# Stepper_Motor3.net
KiCad netlist of a schematic drawn in Altium Designer
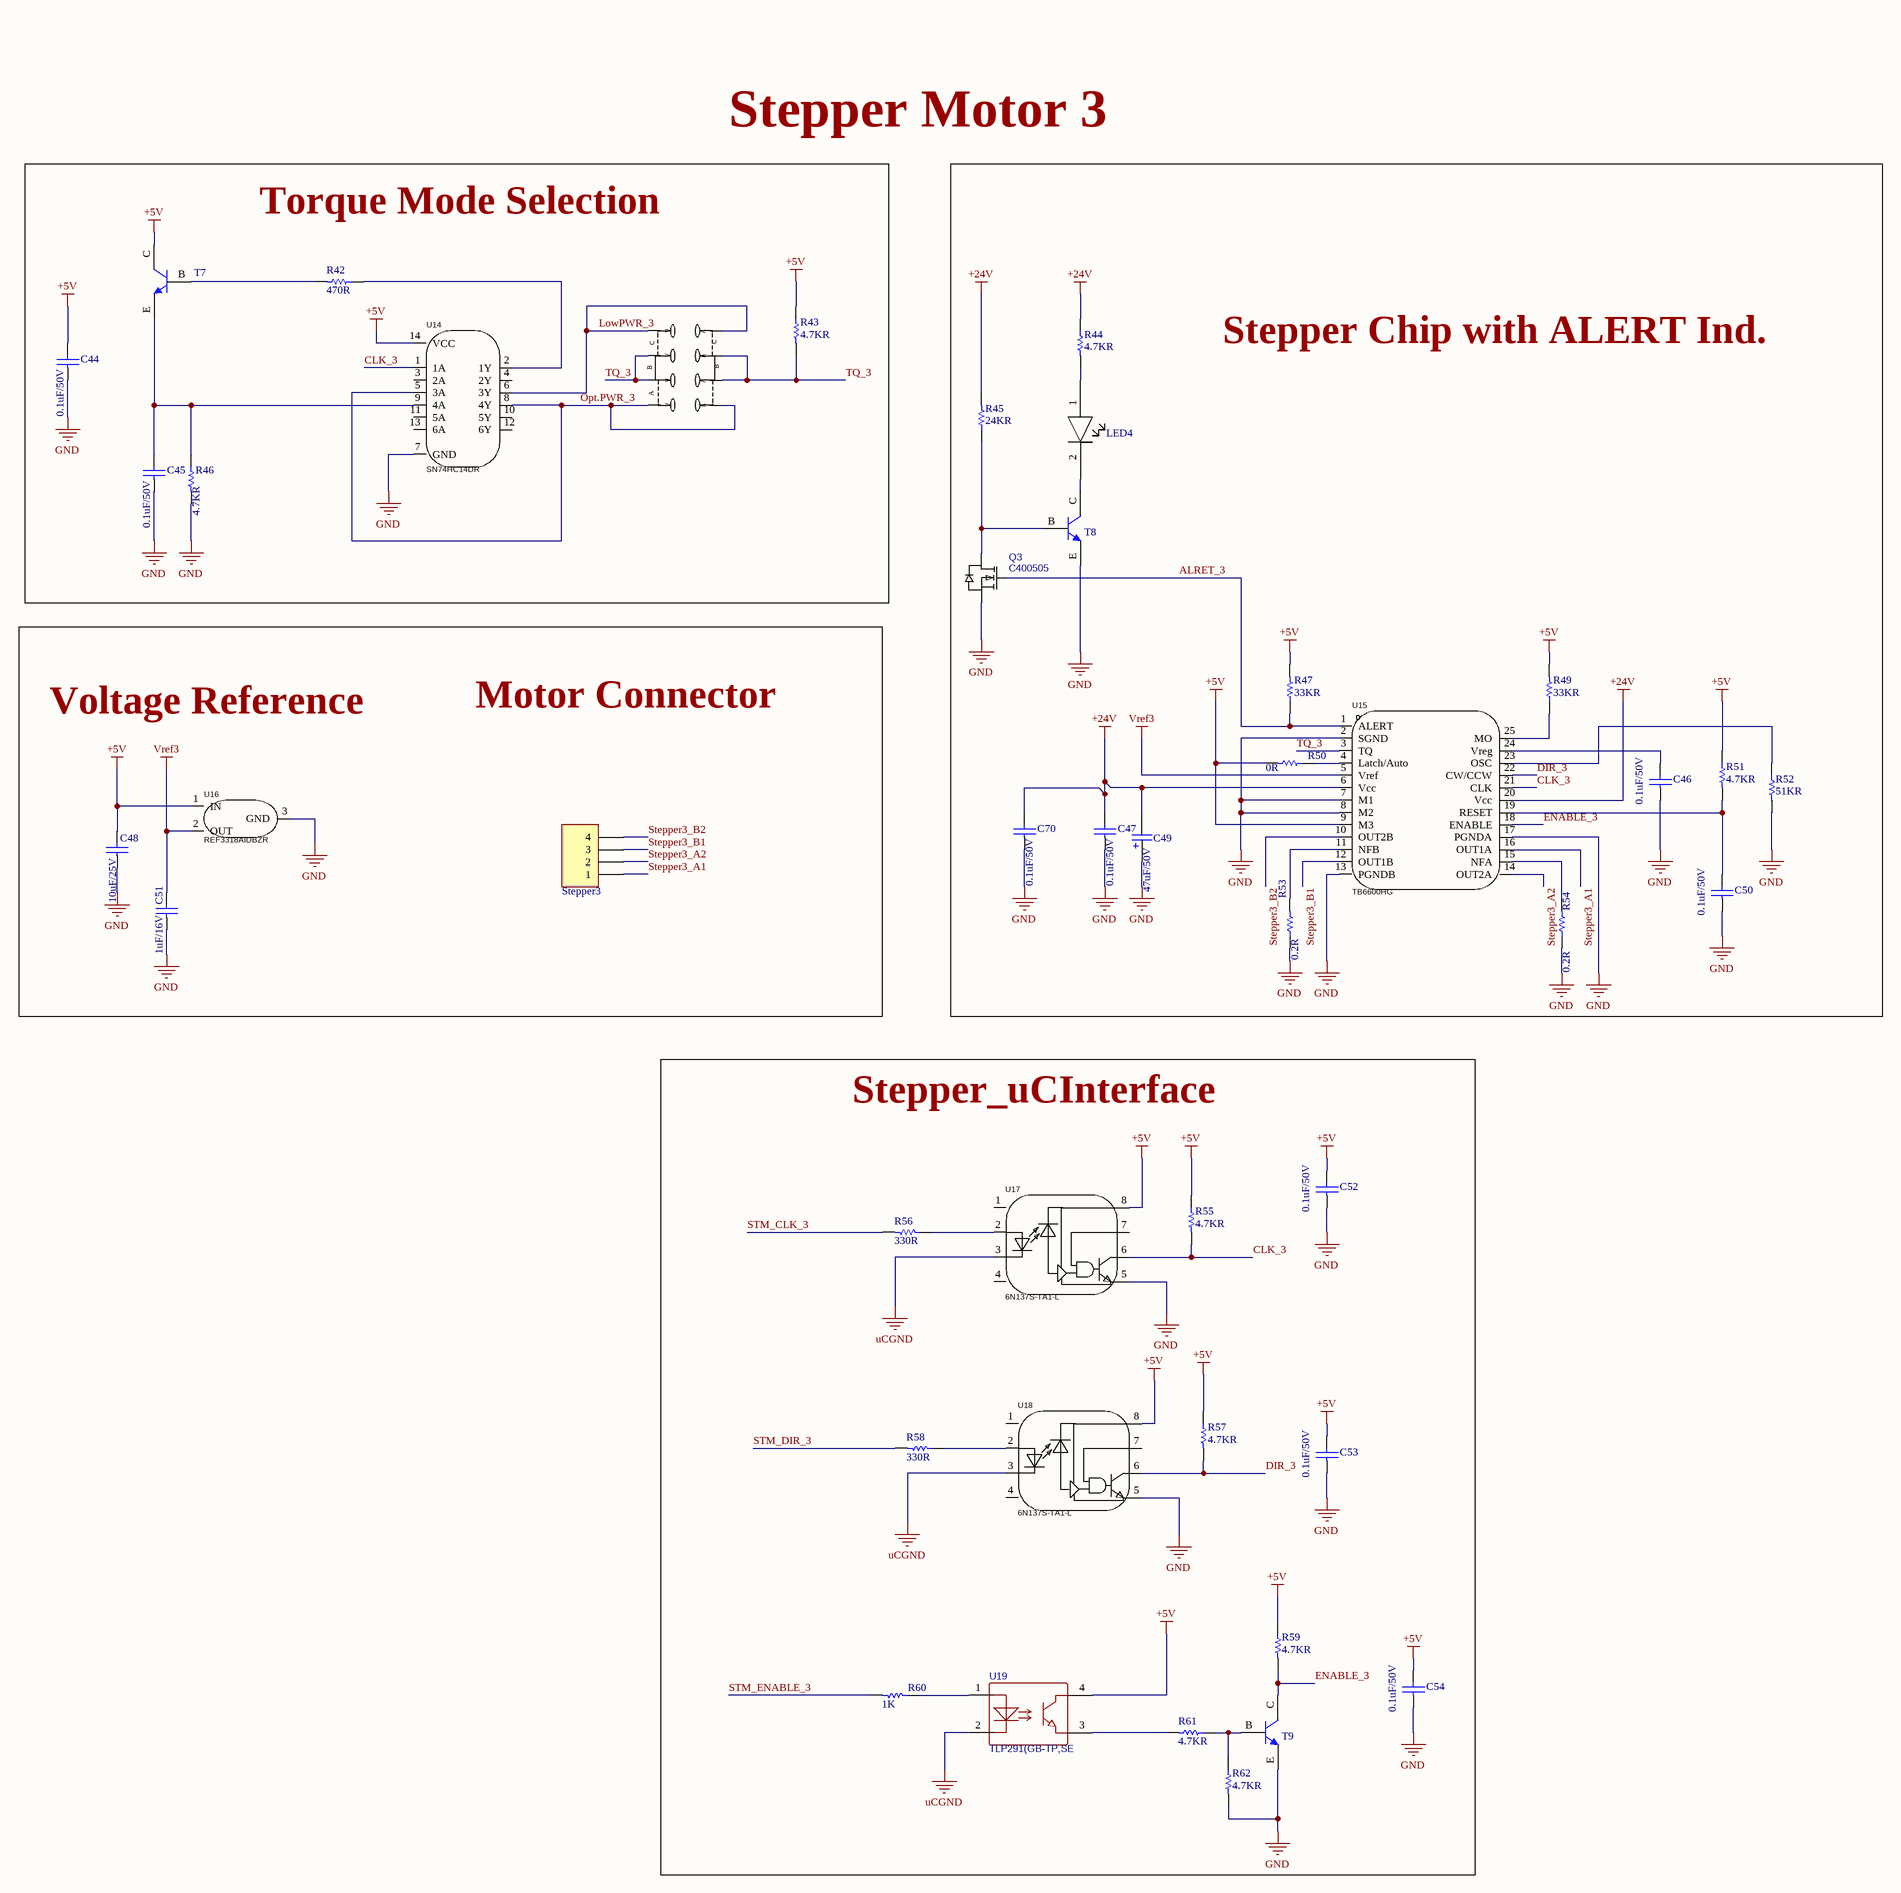
[diagram p0: Stepper Motor3.SchDoc]

(export (version "E")
  (design (tool "Eeschema 10.0.6"))
  (components
    (comp (ref "C44")
      (value "0.1uF/50V")
      (footprint "PCBComponent_1")
      (description "C1591")
      (fields (field (name "CREATED BY") "NourAldin"))
      (libsource (lib "0603 Capacitor") (part "0603 Capacitor"))
    )
    (comp (ref "C45")
      (value "0.1uF/50V")
      (footprint "PCBComponent_1")
      (description "C1591")
      (fields (field (name "CREATED BY") "NourAldin"))
      (libsource (lib "0603 Capacitor") (part "0603 Capacitor"))
    )
    (comp (ref "C46")
      (value "0.1uF/50V")
      (footprint "PCBComponent_1")
      (description "C1591")
      (fields (field (name "CREATED BY") "NourAldin"))
      (libsource (lib "0603 Capacitor") (part "0603 Capacitor"))
    )
    (comp (ref "C47")
      (value "0.1uF/50V")
      (footprint "PCBComponent_1")
      (description "C1591")
      (fields (field (name "CREATED BY") "NourAldin"))
      (libsource (lib "0603 Capacitor") (part "0603 Capacitor"))
    )
    (comp (ref "C48")
      (value "10uF/25V")
      (footprint "PCBComponent_1")
      (description "C96446")
      (fields (field (name "CREATED BY") "NourAldin"))
      (libsource (lib "0603 Capacitor") (part "0603 Capacitor"))
    )
    (comp (ref "C49")
      (value "47uF/50V")
      (footprint "CAPLEAD_D6.3mm")
      (description "C45100")
      (fields
        (field (name "MANUFACTURER") "KEMET")
        (field (name "MANUFACTURER PART NUMBER") "A759EQ475M2AAAE160")
      )
      (libsource (lib "GlobalLib") (part "A759EQ475M2AAAE160"))
    )
    (comp (ref "C50")
      (value "0.1uF/50V")
      (footprint "PCBComponent_1")
      (description "C1591")
      (fields (field (name "CREATED BY") "NourAldin"))
      (libsource (lib "0603 Capacitor") (part "0603 Capacitor"))
    )
    (comp (ref "C51")
      (value "1uF/16V")
      (footprint "PCBComponent_1")
      (description "C1592")
      (fields (field (name "CREATED BY") "NourAldin"))
      (libsource (lib "0603 Capacitor") (part "0603 Capacitor"))
    )
    (comp (ref "C52")
      (value "0.1uF/50V")
      (footprint "PCBComponent_1")
      (description "C1591")
      (fields (field (name "CREATED BY") "NourAldin"))
      (libsource (lib "0603 Capacitor") (part "0603 Capacitor"))
    )
    (comp (ref "C53")
      (value "0.1uF/50V")
      (footprint "PCBComponent_1")
      (description "C1591")
      (fields (field (name "CREATED BY") "NourAldin"))
      (libsource (lib "0603 Capacitor") (part "0603 Capacitor"))
    )
    (comp (ref "C54")
      (value "0.1uF/50V")
      (footprint "PCBComponent_1")
      (description "C1591")
      (fields (field (name "CREATED BY") "NourAldin"))
      (libsource (lib "0603 Capacitor") (part "0603 Capacitor"))
    )
    (comp (ref "C70")
      (value "0.1uF/50V")
      (footprint "PCBComponent_1")
      (description "C1591")
      (fields (field (name "CREATED BY") "NourAldin"))
      (libsource (lib "0603 Capacitor") (part "0603 Capacitor"))
    )
    (comp (ref "LED4")
      (value "1206 LED")
      (footprint "1206 LED")
      (description "C434438")
      (fields (field (name "CREATED BY") "NourAldin"))
      (libsource (lib "1206 LED") (part "1206 LED"))
    )
    (comp (ref "Q3")
      (value "C400505")
      (footprint "SOT-23-3_L2.9-W1.3-P1.90-LS2.4-BR")
      (fields
        (field (name "MANUFACTURER") "YANGJIE(扬杰)")
        (field (name "MANUFACTURER PART") "BSS138")
        (field (name "CONTRIBUTOR") "LCSC")
      )
      (libsource (lib "DIVERSE") (part "BSS138_MOSFET"))
    )
    (comp (ref "R42")
      (value "470R")
      (footprint "RESC1608X06N")
      (description "C114669")
      (fields (field (name "CREATED BY") "NourAldin"))
      (libsource (lib "0603 Resistor") (part "0603 Resistor"))
    )
    (comp (ref "R43")
      (value "4.7KR")
      (footprint "R0402")
      (description "C105871")
      (libsource (lib "DIVERSE") (part "0402 Resistor"))
    )
    (comp (ref "R44")
      (value "4.7KR")
      (footprint "R0402")
      (description "C105871")
      (libsource (lib "DIVERSE") (part "0402 Resistor"))
    )
    (comp (ref "R45")
      (value "24KR")
      (footprint "RESC1608X06N")
      (description "C2930081")
      (fields (field (name "CREATED BY") "NourAldin"))
      (libsource (lib "0603 Resistor") (part "0603 Resistor"))
    )
    (comp (ref "R46")
      (value "4.7KR")
      (footprint "R0402")
      (description "C105871")
      (libsource (lib "DIVERSE") (part "0402 Resistor"))
    )
    (comp (ref "R47")
      (value "33KR")
      (footprint "RESC1608X06N")
      (description "C126359")
      (fields (field (name "CREATED BY") "NourAldin"))
      (libsource (lib "0603 Resistor") (part "0603 Resistor"))
    )
    (comp (ref "R49")
      (value "33KR")
      (footprint "RESC1608X06N")
      (description "C126359")
      (fields (field (name "CREATED BY") "NourAldin"))
      (libsource (lib "0603 Resistor") (part "0603 Resistor"))
    )
    (comp (ref "R50")
      (value "0R")
      (footprint "RESC1608X06N")
      (description "C100044")
      (fields (field (name "CREATED BY") "NourAldin"))
      (libsource (lib "0603 Resistor") (part "0603 Resistor"))
    )
    (comp (ref "R51")
      (value "4.7KR")
      (footprint "R0402")
      (description "C105871")
      (libsource (lib "DIVERSE") (part "0402 Resistor"))
    )
    (comp (ref "R52")
      (value "51KR")
      (footprint "R0402")
      (description "C107230")
      (libsource (lib "DIVERSE") (part "0402 Resistor"))
    )
    (comp (ref "R53")
      (value "0.2R")
      (footprint "RESC6431X12N")
      (description "C2903473")
      (fields (field (name "CREATED BY") "NourAldin"))
      (libsource (lib "2512 Resistor") (part "2512 Resistor"))
    )
    (comp (ref "R54")
      (value "0.2R")
      (footprint "RESC6431X12N")
      (description "C2903473")
      (fields (field (name "CREATED BY") "NourAldin"))
      (libsource (lib "2512 Resistor") (part "2512 Resistor"))
    )
    (comp (ref "R55")
      (value "4.7KR")
      (footprint "R0402")
      (description "C105871")
      (libsource (lib "DIVERSE") (part "0402 Resistor"))
    )
    (comp (ref "R56")
      (value "330R")
      (footprint "R0402")
      (description "C105875")
      (libsource (lib "DIVERSE") (part "0402 Resistor"))
    )
    (comp (ref "R57")
      (value "4.7KR")
      (footprint "R0402")
      (description "C105871")
      (libsource (lib "DIVERSE") (part "0402 Resistor"))
    )
    (comp (ref "R58")
      (value "330R")
      (footprint "R0402")
      (description "C105875")
      (libsource (lib "DIVERSE") (part "0402 Resistor"))
    )
    (comp (ref "R59")
      (value "4.7KR")
      (footprint "R0402")
      (description "C105871")
      (libsource (lib "DIVERSE") (part "0402 Resistor"))
    )
    (comp (ref "R60")
      (value "1K")
      (footprint "R0402")
      (description "C106235")
      (libsource (lib "DIVERSE") (part "0402 Resistor"))
    )
    (comp (ref "R61")
      (value "4.7KR")
      (footprint "R0402")
      (description "C105871")
      (libsource (lib "DIVERSE") (part "0402 Resistor"))
    )
    (comp (ref "R62")
      (value "4.7KR")
      (footprint "R0402")
      (description "C105871")
      (libsource (lib "DIVERSE") (part "0402 Resistor"))
    )
    (comp (ref "Stepper3")
      (value "Header 4 Pin Polar")
      (footprint "PCBComponent_1")
      (libsource (lib "Header 4 Pin Polar") (part "Header 4 Pin Polar"))
    )
    (comp (ref "SW3")
      (value "MST23D19G2")
      (footprint "SW-SMD_MST23D19G2")
      (description "C431545")
      (fields (field (name "MANUFACTURER") "SHOU HAN(首韩)"))
      (libsource (lib "LIB") (part "MST23D19G2"))
    )
    (comp (ref "T7")
      (value "MMBT3904 Transistor")
      (footprint "MMBT3904")
      (description "C108429")
      (fields (field (name "CREATED BY") "NourAldin"))
      (libsource (lib "MMBT3904 Transistor") (part "MMBT3904 Transistor"))
    )
    (comp (ref "T8")
      (value "MMBT3904 Transistor")
      (footprint "MMBT3904")
      (description "C108429")
      (fields (field (name "CREATED BY") "NourAldin"))
      (libsource (lib "MMBT3904 Transistor") (part "MMBT3904 Transistor"))
    )
    (comp (ref "T9")
      (value "MMBT3904 Transistor")
      (footprint "MMBT3904")
      (description "C108429")
      (fields (field (name "CREATED BY") "NourAldin"))
      (libsource (lib "MMBT3904 Transistor") (part "MMBT3904 Transistor"))
    )
    (comp (ref "U14")
      (value "SN74HC14DR")
      (footprint "SOIC-14_L8.7-W3.9-P1.27-LS6.0-BL")
      (description "C6820")
      (fields (field (name "MANUFACTURER") "TI(德州仪器)"))
      (libsource (lib "LIB") (part "SN74HC14DR"))
    )
    (comp (ref "U15")
      (value "TB6600HG")
      (footprint "HZIP25-P-1.00F")
      (description "C66042")
      (fields (field (name "MANUFACTURER") "TOSHIBA(东芝)"))
      (libsource (lib "LIB") (part "TB6600HG"))
    )
    (comp (ref "U16")
      (value "REF3318AIDBZR")
      (footprint "SOT-23-3_L2.9-W1.3-P1.90-LS2.4-BR")
      (description "C115877")
      (fields (field (name "MANUFACTURER") "TI(德州仪器)") (field (name "TOLERANCE") "±0.15%"))
      (libsource (lib "LIB") (part "REF3318AIDBZR"))
    )
    (comp (ref "U17")
      (value "6N137S-TA1-L")
      (footprint "SOP-8_L9.8-W6.6-P2.54-LS10.3-BL")
      (description "C92651")
      (fields (field (name "MANUFACTURER") "LITEON(光宝)"))
      (libsource (lib "LIB") (part "6N137S-TA1-L"))
    )
    (comp (ref "U18")
      (value "6N137S-TA1-L")
      (footprint "SOP-8_L9.8-W6.6-P2.54-LS10.3-BL")
      (description "C92651")
      (fields (field (name "MANUFACTURER") "LITEON(光宝)"))
      (libsource (lib "LIB") (part "6N137S-TA1-L"))
    )
    (comp (ref "U19")
      (value "TLP291(GB-TP,SE")
      (footprint "SOP-4-1.27mm")
      (description "C55144")
      (libsource (lib "CO2_Lib") (part "TLP291(GB-TP,SE(T"))
    )
  )
  (nets
    (net (code "1") (name "+5V") (class "Default")
      (node (ref "C44") (pin "2") (pinfunction "2_2") (pintype "passive"))
      (node (ref "C48") (pin "2") (pinfunction "2_2") (pintype "passive"))
      (node (ref "C52") (pin "2") (pinfunction "2_2") (pintype "passive"))
      (node (ref "C53") (pin "2") (pinfunction "2_2") (pintype "passive"))
      (node (ref "C54") (pin "2") (pinfunction "2_2") (pintype "passive"))
      (node (ref "R43") (pin "1") (pinfunction "1_1") (pintype "passive"))
      (node (ref "R47") (pin "2") (pinfunction "2_2") (pintype "passive"))
      (node (ref "R49") (pin "2") (pinfunction "2_2") (pintype "passive"))
      (node (ref "R50") (pin "2") (pinfunction "2_2") (pintype "passive"))
      (node (ref "R51") (pin "1") (pinfunction "1_1") (pintype "passive"))
      (node (ref "R55") (pin "1") (pinfunction "1_1") (pintype "passive"))
      (node (ref "R57") (pin "1") (pinfunction "1_1") (pintype "passive"))
      (node (ref "R59") (pin "1") (pinfunction "1_1") (pintype "passive"))
      (node (ref "T7") (pin "C") (pinfunction "C_C") (pintype "passive"))
      (node (ref "U14") (pin "14") (pinfunction "VCC_14") (pintype "passive"))
      (node (ref "U15") (pin "9") (pinfunction "M3_9") (pintype "passive"))
      (node (ref "U16") (pin "1") (pinfunction "IN_1") (pintype "passive"))
      (node (ref "U17") (pin "8") (pinfunction "8_8") (pintype "passive"))
      (node (ref "U18") (pin "8") (pinfunction "8_8") (pintype "passive"))
      (node (ref "U19") (pin "4") (pinfunction "4_4") (pintype "passive"))
    )
    (net (code "2") (name "+24V") (class "Default")
      (node (ref "C47") (pin "2") (pinfunction "2_2") (pintype "passive"))
      (node (ref "C49") (pin "2") (pinfunction "2_2") (pintype "passive"))
      (node (ref "C70") (pin "2") (pinfunction "2_2") (pintype "passive"))
      (node (ref "R44") (pin "1") (pinfunction "1_1") (pintype "passive"))
      (node (ref "R45") (pin "2") (pinfunction "2_2") (pintype "passive"))
      (node (ref "U15") (pin "20") (pinfunction "Vcc_20") (pintype "passive"))
      (node (ref "U15") (pin "6") (pinfunction "Vcc_6") (pintype "passive"))
    )
    (net (code "3") (name "/ALRET_3") (class "Default")
      (node (ref "Q3") (pin "1") (pinfunction "G_1") (pintype "passive"))
      (node (ref "R47") (pin "1") (pinfunction "1_1") (pintype "passive"))
      (node (ref "U15") (pin "1") (pinfunction "ALERT_1") (pintype "passive"))
    )
    (net (code "4") (name "/CLK_3") (class "Default")
      (node (ref "R55") (pin "2") (pinfunction "2_2") (pintype "passive"))
      (node (ref "U14") (pin "1") (pinfunction "1A_1") (pintype "passive"))
      (node (ref "U15") (pin "21") (pinfunction "CLK_21") (pintype "passive"))
      (node (ref "U17") (pin "6") (pinfunction "6_6") (pintype "passive"))
    )
    (net (code "5") (name "/DIR_3") (class "Default")
      (node (ref "R57") (pin "2") (pinfunction "2_2") (pintype "passive"))
      (node (ref "U15") (pin "22") (pinfunction "CW/CCW_22") (pintype "passive"))
      (node (ref "U18") (pin "6") (pinfunction "6_6") (pintype "passive"))
    )
    (net (code "6") (name "/ENABLE_3") (class "Default")
      (node (ref "R59") (pin "2") (pinfunction "2_2") (pintype "passive"))
      (node (ref "T9") (pin "C") (pinfunction "C_C") (pintype "passive"))
      (node (ref "U15") (pin "18") (pinfunction "ENABLE_18") (pintype "passive"))
    )
    (net (code "7") (name "/LowPWR_3") (class "Default")
      (node (ref "SW3") (pin "4") (pinfunction "4_4") (pintype "passive"))
      (node (ref "SW3") (pin "5") (pinfunction "5_5") (pintype "passive"))
      (node (ref "U14") (pin "6") (pinfunction "3Y_6") (pintype "passive"))
    )
    (net (code "8") (name "/Opt.PWR_3") (class "Default")
      (node (ref "SW3") (pin "1") (pinfunction "1_1") (pintype "passive"))
      (node (ref "SW3") (pin "8") (pinfunction "8_8") (pintype "passive"))
      (node (ref "U14") (pin "5") (pinfunction "3A_5") (pintype "passive"))
      (node (ref "U14") (pin "8") (pinfunction "4Y_8") (pintype "passive"))
    )
    (net (code "9") (name "/STM_CLK_3") (class "Default")
      (node (ref "R56") (pin "2") (pinfunction "2_2") (pintype "passive"))
    )
    (net (code "10") (name "/STM_DIR_3") (class "Default")
      (node (ref "R58") (pin "2") (pinfunction "2_2") (pintype "passive"))
    )
    (net (code "11") (name "/STM_ENABLE_3") (class "Default")
      (node (ref "R60") (pin "2") (pinfunction "2_2") (pintype "passive"))
    )
    (net (code "12") (name "/Stepper3_A1") (class "Default")
      (node (ref "Stepper3") (pin "1") (pinfunction "1_1") (pintype "passive"))
      (node (ref "U15") (pin "16") (pinfunction "OUT1A_16") (pintype "passive"))
    )
    (net (code "13") (name "/Stepper3_A2") (class "Default")
      (node (ref "Stepper3") (pin "2") (pinfunction "2_2") (pintype "passive"))
      (node (ref "U15") (pin "14") (pinfunction "OUT2A_14") (pintype "passive"))
    )
    (net (code "14") (name "/Stepper3_B1") (class "Default")
      (node (ref "Stepper3") (pin "3") (pinfunction "3_3") (pintype "passive"))
      (node (ref "U15") (pin "12") (pinfunction "OUT1B_12") (pintype "passive"))
    )
    (net (code "15") (name "/Stepper3_B2") (class "Default")
      (node (ref "Stepper3") (pin "4") (pinfunction "4_4") (pintype "passive"))
      (node (ref "U15") (pin "10") (pinfunction "OUT2B_10") (pintype "passive"))
    )
    (net (code "16") (name "/TQ_3") (class "Default")
      (node (ref "R43") (pin "2") (pinfunction "2_2") (pintype "passive"))
      (node (ref "SW3") (pin "2") (pinfunction "2_2") (pintype "passive"))
      (node (ref "SW3") (pin "3") (pinfunction "3_3") (pintype "passive"))
      (node (ref "SW3") (pin "6") (pinfunction "6_6") (pintype "passive"))
      (node (ref "SW3") (pin "7") (pinfunction "7_7") (pintype "passive"))
      (node (ref "U15") (pin "3") (pinfunction "TQ_3") (pintype "passive"))
    )
    (net (code "17") (name "GND") (class "Default")
      (node (ref "C44") (pin "1") (pinfunction "1_1") (pintype "passive"))
      (node (ref "C45") (pin "1") (pinfunction "1_1") (pintype "passive"))
      (node (ref "C46") (pin "1") (pinfunction "1_1") (pintype "passive"))
      (node (ref "C47") (pin "1") (pinfunction "1_1") (pintype "passive"))
      (node (ref "C48") (pin "1") (pinfunction "1_1") (pintype "passive"))
      (node (ref "C49") (pin "1") (pinfunction "1_1") (pintype "passive"))
      (node (ref "C50") (pin "1") (pinfunction "1_1") (pintype "passive"))
      (node (ref "C51") (pin "1") (pinfunction "1_1") (pintype "passive"))
      (node (ref "C52") (pin "1") (pinfunction "1_1") (pintype "passive"))
      (node (ref "C53") (pin "1") (pinfunction "1_1") (pintype "passive"))
      (node (ref "C54") (pin "1") (pinfunction "1_1") (pintype "passive"))
      (node (ref "C70") (pin "1") (pinfunction "1_1") (pintype "passive"))
      (node (ref "Q3") (pin "2") (pinfunction "S_2") (pintype "passive"))
      (node (ref "R46") (pin "2") (pinfunction "2_2") (pintype "passive"))
      (node (ref "R52") (pin "2") (pinfunction "2_2") (pintype "passive"))
      (node (ref "R53") (pin "1") (pinfunction "1_1") (pintype "passive"))
      (node (ref "R54") (pin "1") (pinfunction "1_1") (pintype "passive"))
      (node (ref "R62") (pin "2") (pinfunction "2_2") (pintype "passive"))
      (node (ref "T8") (pin "E") (pinfunction "E_E") (pintype "passive"))
      (node (ref "T9") (pin "E") (pinfunction "E_E") (pintype "passive"))
      (node (ref "U14") (pin "7") (pinfunction "GND_7") (pintype "passive"))
      (node (ref "U15") (pin "13") (pinfunction "PGNDB_13") (pintype "passive"))
      (node (ref "U15") (pin "17") (pinfunction "PGNDA_17") (pintype "passive"))
      (node (ref "U15") (pin "2") (pinfunction "SGND_2") (pintype "passive"))
      (node (ref "U15") (pin "7") (pinfunction "M1_7") (pintype "passive"))
      (node (ref "U15") (pin "8") (pinfunction "M2_8") (pintype "passive"))
      (node (ref "U16") (pin "3") (pinfunction "GND_3") (pintype "passive"))
      (node (ref "U17") (pin "5") (pinfunction "5_5") (pintype "passive"))
      (node (ref "U18") (pin "5") (pinfunction "5_5") (pintype "passive"))
    )
    (net (code "18") (name "Net-(LED4-Pad1)") (class "Default")
      (node (ref "LED4") (pin "1") (pinfunction "1_1") (pintype "passive"))
      (node (ref "R44") (pin "2") (pinfunction "2_2") (pintype "passive"))
    )
    (net (code "19") (name "Net-(LED4-Pad2)") (class "Default")
      (node (ref "LED4") (pin "2") (pinfunction "2_2") (pintype "passive"))
      (node (ref "T8") (pin "C") (pinfunction "C_C") (pintype "passive"))
    )
    (net (code "20") (name "Net-(Q3-D)") (class "Default")
      (node (ref "Q3") (pin "3") (pinfunction "D_3") (pintype "passive"))
      (node (ref "R45") (pin "1") (pinfunction "1_1") (pintype "passive"))
      (node (ref "T8") (pin "B") (pinfunction "B_B") (pintype "passive"))
    )
    (net (code "21") (name "Net-(R42-Pad2)") (class "Default")
      (node (ref "R42") (pin "2") (pinfunction "2_2") (pintype "passive"))
      (node (ref "T7") (pin "B") (pinfunction "B_B") (pintype "passive"))
    )
    (net (code "22") (name "Net-(R56-Pad1)") (class "Default")
      (node (ref "R56") (pin "1") (pinfunction "1_1") (pintype "passive"))
      (node (ref "U17") (pin "2") (pinfunction "2_2") (pintype "passive"))
    )
    (net (code "23") (name "Net-(R58-Pad1)") (class "Default")
      (node (ref "R58") (pin "1") (pinfunction "1_1") (pintype "passive"))
      (node (ref "U18") (pin "2") (pinfunction "2_2") (pintype "passive"))
    )
    (net (code "24") (name "Net-(R60-Pad1)") (class "Default")
      (node (ref "R60") (pin "1") (pinfunction "1_1") (pintype "passive"))
      (node (ref "U19") (pin "1") (pinfunction "1_1") (pintype "passive"))
    )
    (net (code "25") (name "Net-(R61-Pad1)") (class "Default")
      (node (ref "R61") (pin "1") (pinfunction "1_1") (pintype "passive"))
      (node (ref "R62") (pin "1") (pinfunction "1_1") (pintype "passive"))
      (node (ref "T9") (pin "B") (pinfunction "B_B") (pintype "passive"))
    )
    (net (code "26") (name "Net-(R61-Pad2)") (class "Default")
      (node (ref "R61") (pin "2") (pinfunction "2_2") (pintype "passive"))
      (node (ref "U19") (pin "3") (pinfunction "3_3") (pintype "passive"))
    )
    (net (code "27") (name "Net-(U14-1Y)") (class "Default")
      (node (ref "R42") (pin "1") (pinfunction "1_1") (pintype "passive"))
      (node (ref "U14") (pin "2") (pinfunction "1Y_2") (pintype "passive"))
    )
    (net (code "28") (name "Net-(U14-4A)") (class "Default")
      (node (ref "C45") (pin "2") (pinfunction "2_2") (pintype "passive"))
      (node (ref "R46") (pin "1") (pinfunction "1_1") (pintype "passive"))
      (node (ref "T7") (pin "E") (pinfunction "E_E") (pintype "passive"))
      (node (ref "U14") (pin "9") (pinfunction "4A_9") (pintype "passive"))
    )
    (net (code "29") (name "Net-(U15-Latch{slash}Auto)") (class "Default")
      (node (ref "R50") (pin "1") (pinfunction "1_1") (pintype "passive"))
      (node (ref "U15") (pin "4") (pinfunction "Latch/Auto_4") (pintype "passive"))
    )
    (net (code "30") (name "Net-(U15-MO)") (class "Default")
      (node (ref "R49") (pin "1") (pinfunction "1_1") (pintype "passive"))
      (node (ref "U15") (pin "25") (pinfunction "MO_25") (pintype "passive"))
    )
    (net (code "31") (name "Net-(U15-NFA)") (class "Default")
      (node (ref "R54") (pin "2") (pinfunction "2_2") (pintype "passive"))
      (node (ref "U15") (pin "15") (pinfunction "NFA_15") (pintype "passive"))
    )
    (net (code "32") (name "Net-(U15-NFB)") (class "Default")
      (node (ref "R53") (pin "2") (pinfunction "2_2") (pintype "passive"))
      (node (ref "U15") (pin "11") (pinfunction "NFB_11") (pintype "passive"))
    )
    (net (code "33") (name "Net-(U15-OSC)") (class "Default")
      (node (ref "R52") (pin "1") (pinfunction "1_1") (pintype "passive"))
      (node (ref "U15") (pin "23") (pinfunction "OSC_23") (pintype "passive"))
    )
    (net (code "34") (name "Net-(U15-RESET)") (class "Default")
      (node (ref "C50") (pin "2") (pinfunction "2_2") (pintype "passive"))
      (node (ref "R51") (pin "2") (pinfunction "2_2") (pintype "passive"))
      (node (ref "U15") (pin "19") (pinfunction "RESET_19") (pintype "passive"))
    )
    (net (code "35") (name "Net-(U15-Vreg)") (class "Default")
      (node (ref "C46") (pin "2") (pinfunction "2_2") (pintype "passive"))
      (node (ref "U15") (pin "24") (pinfunction "Vreg_24") (pintype "passive"))
    )
    (net (code "36") (name "Vref3") (class "Default")
      (node (ref "C51") (pin "2") (pinfunction "2_2") (pintype "passive"))
      (node (ref "U15") (pin "5") (pinfunction "Vref_5") (pintype "passive"))
      (node (ref "U16") (pin "2") (pinfunction "OUT_2") (pintype "passive"))
    )
    (net (code "37") (name "uCGND") (class "Default")
      (node (ref "U17") (pin "3") (pinfunction "3_3") (pintype "passive"))
      (node (ref "U18") (pin "3") (pinfunction "3_3") (pintype "passive"))
      (node (ref "U19") (pin "2") (pinfunction "2_2") (pintype "passive"))
    )
    (net (code "38") (name "unconnected-(U14-2A-Pad3)") (class "Default")
      (node (ref "U14") (pin "3") (pinfunction "2A_3") (pintype "passive"))
    )
    (net (code "39") (name "unconnected-(U14-2Y-Pad4)") (class "Default")
      (node (ref "U14") (pin "4") (pinfunction "2Y_4") (pintype "passive"))
    )
    (net (code "40") (name "unconnected-(U14-5A-Pad11)") (class "Default")
      (node (ref "U14") (pin "11") (pinfunction "5A_11") (pintype "passive"))
    )
    (net (code "41") (name "unconnected-(U14-5Y-Pad10)") (class "Default")
      (node (ref "U14") (pin "10") (pinfunction "5Y_10") (pintype "passive"))
    )
    (net (code "42") (name "unconnected-(U14-6A-Pad13)") (class "Default")
      (node (ref "U14") (pin "13") (pinfunction "6A_13") (pintype "passive"))
    )
    (net (code "43") (name "unconnected-(U14-6Y-Pad12)") (class "Default")
      (node (ref "U14") (pin "12") (pinfunction "6Y_12") (pintype "passive"))
    )
    (net (code "44") (name "unconnected-(U17-NC-Pad1)") (class "Default")
      (node (ref "U17") (pin "1") (pinfunction "NC_1") (pintype "passive"))
    )
    (net (code "45") (name "unconnected-(U17-NC-Pad4)") (class "Default")
      (node (ref "U17") (pin "4") (pinfunction "NC_4") (pintype "passive"))
    )
    (net (code "46") (name "unconnected-(U17-Pad7)") (class "Default")
      (node (ref "U17") (pin "7") (pinfunction "7_7") (pintype "passive"))
    )
    (net (code "47") (name "unconnected-(U18-NC-Pad1)") (class "Default")
      (node (ref "U18") (pin "1") (pinfunction "NC_1") (pintype "passive"))
    )
    (net (code "48") (name "unconnected-(U18-NC-Pad4)") (class "Default")
      (node (ref "U18") (pin "4") (pinfunction "NC_4") (pintype "passive"))
    )
    (net (code "49") (name "unconnected-(U18-Pad7)") (class "Default")
      (node (ref "U18") (pin "7") (pinfunction "7_7") (pintype "passive"))
    )
  )
)
